# lpf-40.net
KiCad netlist of a schematic drawn in EAGLE
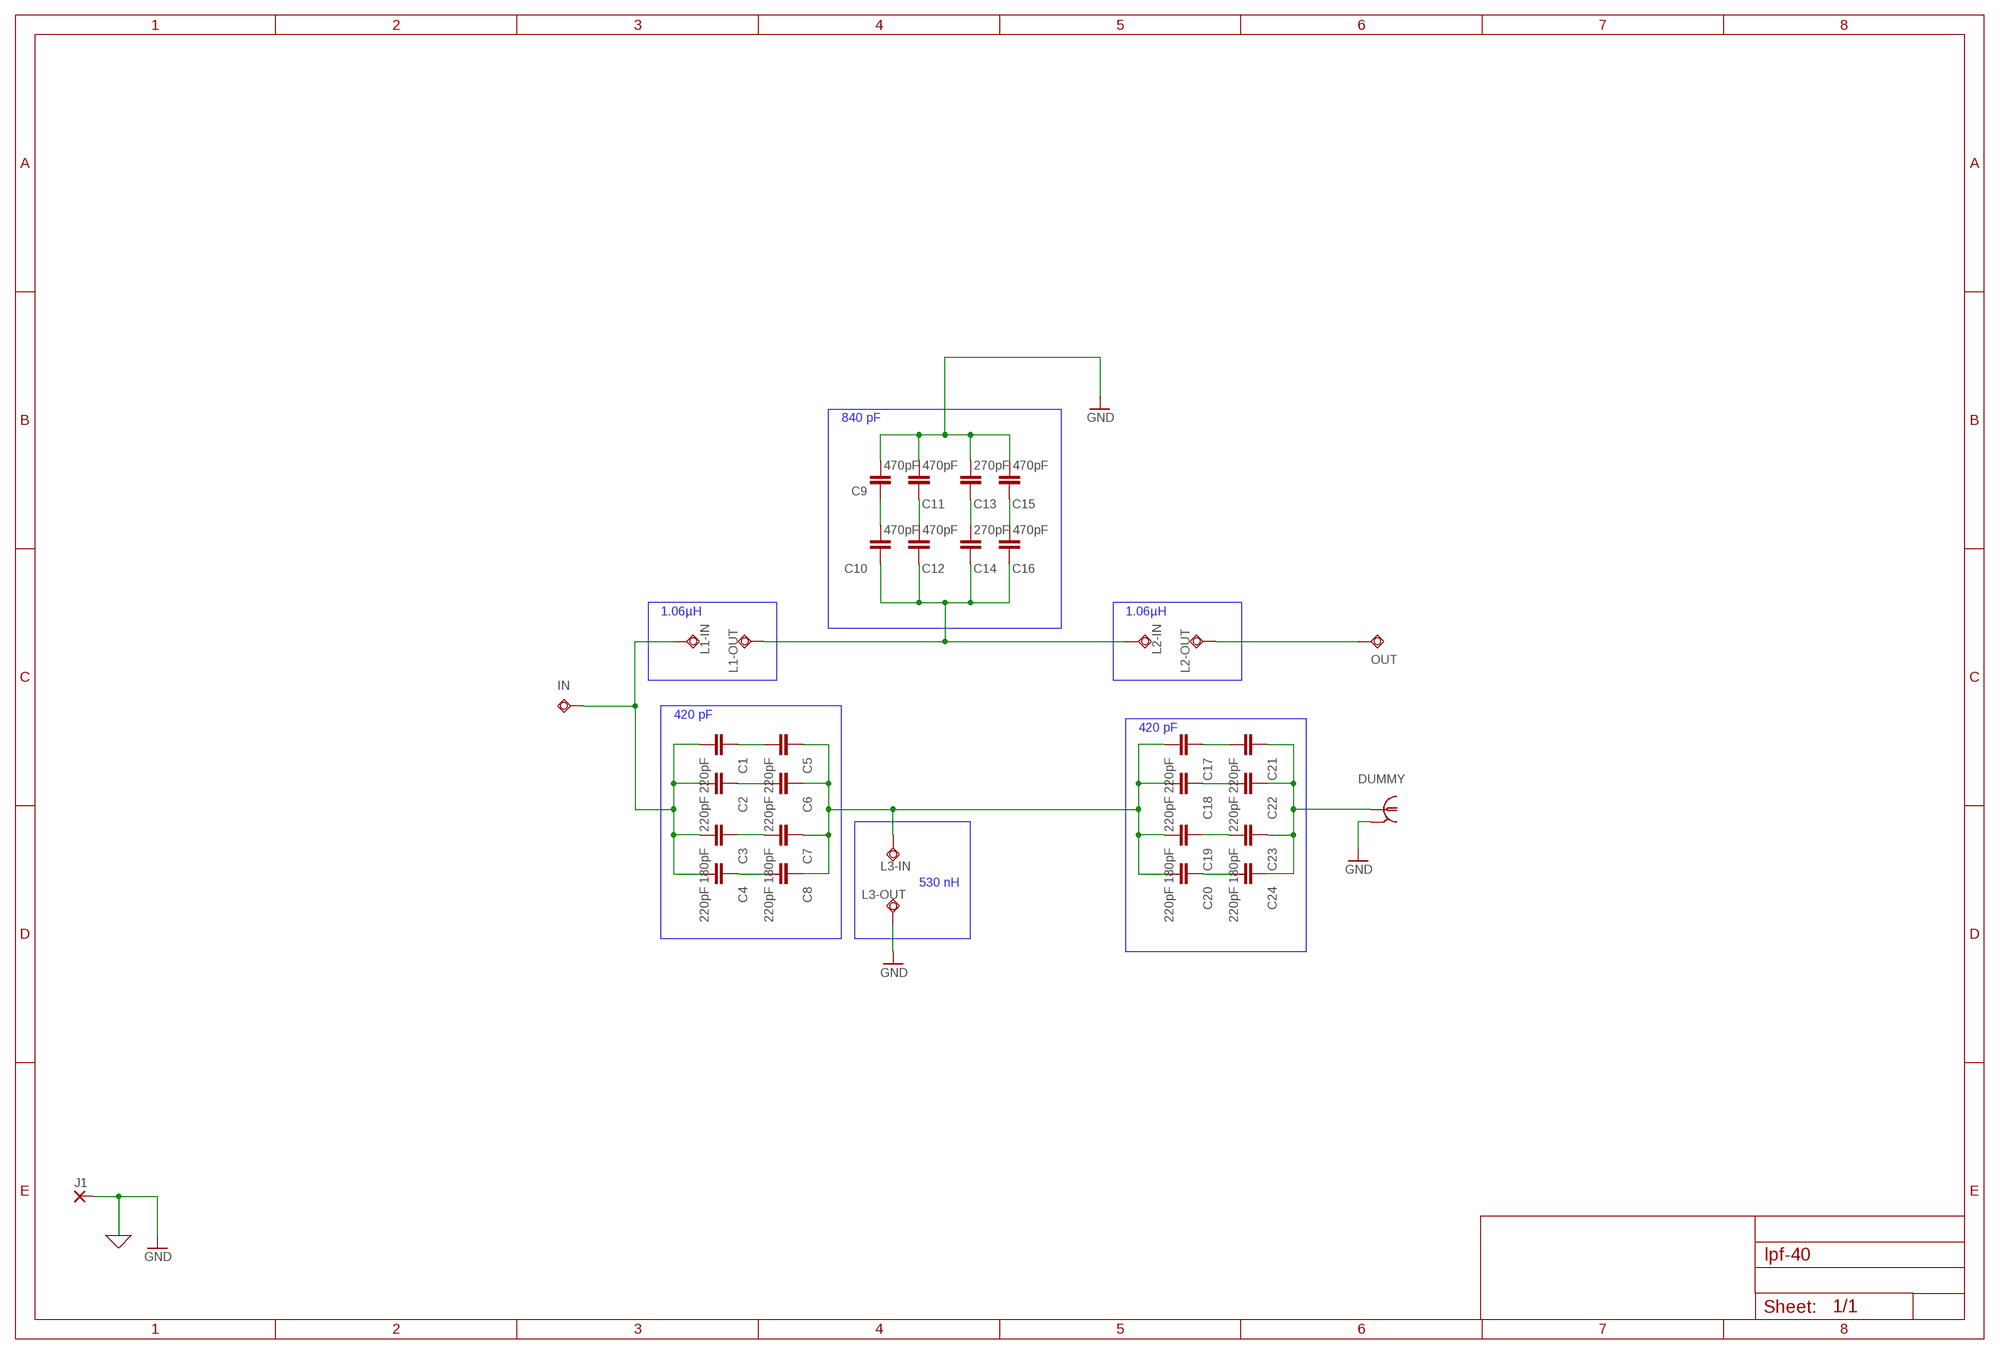
[diagram p0: schematic, sheet 1]

(export (version "E")
  (design (tool "Eeschema 10.0.6"))
  (components
    (comp (ref "C1")
      (value "220pF")
      (footprint "eagle-import:1206")
      (libsource (lib "eagle-import") (part "C-1206"))
    )
    (comp (ref "C2")
      (value "220pF")
      (footprint "eagle-import:1206")
      (libsource (lib "eagle-import") (part "C-1206"))
    )
    (comp (ref "C3")
      (value "180pF")
      (footprint "eagle-import:1206")
      (libsource (lib "eagle-import") (part "C-1206"))
    )
    (comp (ref "C4")
      (value "220pF")
      (footprint "eagle-import:1206")
      (libsource (lib "eagle-import") (part "C-1206"))
    )
    (comp (ref "C5")
      (value "220pF")
      (footprint "eagle-import:1206")
      (libsource (lib "eagle-import") (part "C-1206"))
    )
    (comp (ref "C6")
      (value "220pF")
      (footprint "eagle-import:1206")
      (libsource (lib "eagle-import") (part "C-1206"))
    )
    (comp (ref "C7")
      (value "180pF")
      (footprint "eagle-import:1206")
      (libsource (lib "eagle-import") (part "C-1206"))
    )
    (comp (ref "C8")
      (value "220pF")
      (footprint "eagle-import:1206")
      (libsource (lib "eagle-import") (part "C-1206"))
    )
    (comp (ref "C9")
      (value "470pF")
      (footprint "eagle-import:1206")
      (libsource (lib "eagle-import") (part "C-1206"))
    )
    (comp (ref "C10")
      (value "470pF")
      (footprint "eagle-import:1206")
      (libsource (lib "eagle-import") (part "C-1206"))
    )
    (comp (ref "C11")
      (value "470pF")
      (footprint "eagle-import:1206")
      (libsource (lib "eagle-import") (part "C-1206"))
    )
    (comp (ref "C12")
      (value "470pF")
      (footprint "eagle-import:1206")
      (libsource (lib "eagle-import") (part "C-1206"))
    )
    (comp (ref "C13")
      (value "270pF")
      (footprint "eagle-import:1206")
      (libsource (lib "eagle-import") (part "C-1206"))
    )
    (comp (ref "C14")
      (value "270pF")
      (footprint "eagle-import:1206")
      (libsource (lib "eagle-import") (part "C-1206"))
    )
    (comp (ref "C15")
      (value "470pF")
      (footprint "eagle-import:1206")
      (libsource (lib "eagle-import") (part "C-1206"))
    )
    (comp (ref "C16")
      (value "470pF")
      (footprint "eagle-import:1206")
      (libsource (lib "eagle-import") (part "C-1206"))
    )
    (comp (ref "C17")
      (value "220pF")
      (footprint "eagle-import:1206")
      (libsource (lib "eagle-import") (part "C-1206"))
    )
    (comp (ref "C18")
      (value "220pF")
      (footprint "eagle-import:1206")
      (libsource (lib "eagle-import") (part "C-1206"))
    )
    (comp (ref "C19")
      (value "180pF")
      (footprint "eagle-import:1206")
      (libsource (lib "eagle-import") (part "C-1206"))
    )
    (comp (ref "C20")
      (value "220pF")
      (footprint "eagle-import:1206")
      (libsource (lib "eagle-import") (part "C-1206"))
    )
    (comp (ref "C21")
      (value "220pF")
      (footprint "eagle-import:1206")
      (libsource (lib "eagle-import") (part "C-1206"))
    )
    (comp (ref "C22")
      (value "220pF")
      (footprint "eagle-import:1206")
      (libsource (lib "eagle-import") (part "C-1206"))
    )
    (comp (ref "C23")
      (value "180pF")
      (footprint "eagle-import:1206")
      (libsource (lib "eagle-import") (part "C-1206"))
    )
    (comp (ref "C24")
      (value "220pF")
      (footprint "eagle-import:1206")
      (libsource (lib "eagle-import") (part "C-1206"))
    )
    (comp (ref "DUMMY")
      (value "SMA-PCB")
      (footprint "eagle-import:SMA-RF")
      (libsource (lib "eagle-import") (part "SMA-PCB"))
    )
    (comp (ref "IN")
      (value "IN")
      (footprint "eagle-import:TP11R")
      (libsource (lib "eagle-import") (part "TPSQTP11R"))
    )
    (comp (ref "J1")
      (value "JUMPER-1")
      (footprint "eagle-import:JUMPER1")
      (libsource (lib "eagle-import") (part "JUMPER-1"))
    )
    (comp (ref "L1-IN")
      (value "L1-IN")
      (footprint "eagle-import:TP11R")
      (libsource (lib "eagle-import") (part "TPSQTP11R"))
    )
    (comp (ref "L1-OUT")
      (value "TPSQTP11R")
      (footprint "eagle-import:TP11R")
      (libsource (lib "eagle-import") (part "TPSQTP11R"))
    )
    (comp (ref "L2-IN")
      (value "TPSQTP11R")
      (footprint "eagle-import:TP11R")
      (libsource (lib "eagle-import") (part "TPSQTP11R"))
    )
    (comp (ref "L2-OUT")
      (value "TPSQTP11R")
      (footprint "eagle-import:TP11R")
      (libsource (lib "eagle-import") (part "TPSQTP11R"))
    )
    (comp (ref "L3-IN")
      (value "TPSQTP11R")
      (footprint "eagle-import:TP11R")
      (libsource (lib "eagle-import") (part "TPSQTP11R"))
    )
    (comp (ref "L3-OUT")
      (value "TPSQTP11R")
      (footprint "eagle-import:TP11R")
      (libsource (lib "eagle-import") (part "TPSQTP11R"))
    )
    (comp (ref "OUT")
      (value "TPSQTP11R")
      (footprint "eagle-import:TP11R")
      (libsource (lib "eagle-import") (part "TPSQTP11R"))
    )
  )
  (nets
    (net (code "1") (name "GND") (class "Default")
      (node (ref "C11") (pin "2") (pinfunction "2_2") (pintype "passive"))
      (node (ref "C13") (pin "2") (pinfunction "2_2") (pintype "passive"))
      (node (ref "C15") (pin "2") (pinfunction "2_2") (pintype "passive"))
      (node (ref "C9") (pin "2") (pinfunction "2_2") (pintype "passive"))
      (node (ref "DUMMY") (pin "2") (pinfunction "2_2") (pintype "passive"))
      (node (ref "DUMMY") (pin "3") (pinfunction "2_3") (pintype "passive"))
      (node (ref "DUMMY") (pin "4") (pinfunction "2_4") (pintype "passive"))
      (node (ref "DUMMY") (pin "5") (pinfunction "2_5") (pintype "passive"))
      (node (ref "J1") (pin "1") (pinfunction "P_1") (pintype "passive"))
      (node (ref "L3-OUT") (pin "TP") (pinfunction "TP_TP") (pintype "input"))
    )
    (net (code "2") (name "Net-(C1-Pad1)") (class "Default")
      (node (ref "C1") (pin "1") (pinfunction "1_1") (pintype "passive"))
      (node (ref "C5") (pin "2") (pinfunction "2_2") (pintype "passive"))
    )
    (net (code "3") (name "Net-(C1-Pad2)") (class "Default")
      (node (ref "C1") (pin "2") (pinfunction "2_2") (pintype "passive"))
      (node (ref "C2") (pin "2") (pinfunction "2_2") (pintype "passive"))
      (node (ref "C3") (pin "2") (pinfunction "2_2") (pintype "passive"))
      (node (ref "C4") (pin "2") (pinfunction "2_2") (pintype "passive"))
      (node (ref "IN") (pin "TP") (pinfunction "TP_TP") (pintype "input"))
      (node (ref "L1-IN") (pin "TP") (pinfunction "TP_TP") (pintype "input"))
    )
    (net (code "4") (name "Net-(C2-Pad1)") (class "Default")
      (node (ref "C2") (pin "1") (pinfunction "1_1") (pintype "passive"))
      (node (ref "C6") (pin "2") (pinfunction "2_2") (pintype "passive"))
    )
    (net (code "5") (name "Net-(C3-Pad1)") (class "Default")
      (node (ref "C3") (pin "1") (pinfunction "1_1") (pintype "passive"))
      (node (ref "C7") (pin "2") (pinfunction "2_2") (pintype "passive"))
    )
    (net (code "6") (name "Net-(C4-Pad1)") (class "Default")
      (node (ref "C4") (pin "1") (pinfunction "1_1") (pintype "passive"))
      (node (ref "C8") (pin "2") (pinfunction "2_2") (pintype "passive"))
    )
    (net (code "7") (name "Net-(C10-Pad1)") (class "Default")
      (node (ref "C10") (pin "1") (pinfunction "1_1") (pintype "passive"))
      (node (ref "C12") (pin "1") (pinfunction "1_1") (pintype "passive"))
      (node (ref "C14") (pin "1") (pinfunction "1_1") (pintype "passive"))
      (node (ref "C16") (pin "1") (pinfunction "1_1") (pintype "passive"))
      (node (ref "L1-OUT") (pin "TP") (pinfunction "TP_TP") (pintype "input"))
      (node (ref "L2-IN") (pin "TP") (pinfunction "TP_TP") (pintype "input"))
    )
    (net (code "8") (name "Net-(C10-Pad2)") (class "Default")
      (node (ref "C10") (pin "2") (pinfunction "2_2") (pintype "passive"))
      (node (ref "C9") (pin "1") (pinfunction "1_1") (pintype "passive"))
    )
    (net (code "9") (name "Net-(C11-Pad1)") (class "Default")
      (node (ref "C11") (pin "1") (pinfunction "1_1") (pintype "passive"))
      (node (ref "C12") (pin "2") (pinfunction "2_2") (pintype "passive"))
    )
    (net (code "10") (name "Net-(C13-Pad1)") (class "Default")
      (node (ref "C13") (pin "1") (pinfunction "1_1") (pintype "passive"))
      (node (ref "C14") (pin "2") (pinfunction "2_2") (pintype "passive"))
    )
    (net (code "11") (name "Net-(C15-Pad1)") (class "Default")
      (node (ref "C15") (pin "1") (pinfunction "1_1") (pintype "passive"))
      (node (ref "C16") (pin "2") (pinfunction "2_2") (pintype "passive"))
    )
    (net (code "12") (name "Net-(C17-Pad1)") (class "Default")
      (node (ref "C17") (pin "1") (pinfunction "1_1") (pintype "passive"))
      (node (ref "C21") (pin "2") (pinfunction "2_2") (pintype "passive"))
    )
    (net (code "13") (name "Net-(C17-Pad2)") (class "Default")
      (node (ref "C17") (pin "2") (pinfunction "2_2") (pintype "passive"))
      (node (ref "C18") (pin "2") (pinfunction "2_2") (pintype "passive"))
      (node (ref "C19") (pin "2") (pinfunction "2_2") (pintype "passive"))
      (node (ref "C20") (pin "2") (pinfunction "2_2") (pintype "passive"))
      (node (ref "C5") (pin "1") (pinfunction "1_1") (pintype "passive"))
      (node (ref "C6") (pin "1") (pinfunction "1_1") (pintype "passive"))
      (node (ref "C7") (pin "1") (pinfunction "1_1") (pintype "passive"))
      (node (ref "C8") (pin "1") (pinfunction "1_1") (pintype "passive"))
      (node (ref "L3-IN") (pin "TP") (pinfunction "TP_TP") (pintype "input"))
    )
    (net (code "14") (name "Net-(C18-Pad1)") (class "Default")
      (node (ref "C18") (pin "1") (pinfunction "1_1") (pintype "passive"))
      (node (ref "C22") (pin "2") (pinfunction "2_2") (pintype "passive"))
    )
    (net (code "15") (name "Net-(C19-Pad1)") (class "Default")
      (node (ref "C19") (pin "1") (pinfunction "1_1") (pintype "passive"))
      (node (ref "C23") (pin "2") (pinfunction "2_2") (pintype "passive"))
    )
    (net (code "16") (name "Net-(C20-Pad1)") (class "Default")
      (node (ref "C20") (pin "1") (pinfunction "1_1") (pintype "passive"))
      (node (ref "C24") (pin "2") (pinfunction "2_2") (pintype "passive"))
    )
    (net (code "17") (name "Net-(C21-Pad1)") (class "Default")
      (node (ref "C21") (pin "1") (pinfunction "1_1") (pintype "passive"))
      (node (ref "C22") (pin "1") (pinfunction "1_1") (pintype "passive"))
      (node (ref "C23") (pin "1") (pinfunction "1_1") (pintype "passive"))
      (node (ref "C24") (pin "1") (pinfunction "1_1") (pintype "passive"))
      (node (ref "DUMMY") (pin "1") (pinfunction "1_1") (pintype "passive"))
    )
    (net (code "18") (name "Net-(L2-OUT-PadTP)") (class "Default")
      (node (ref "L2-OUT") (pin "TP") (pinfunction "TP_TP") (pintype "input"))
      (node (ref "OUT") (pin "TP") (pinfunction "TP_TP") (pintype "input"))
    )
  )
)
